# Potentiostat.net
KiCad netlist of a schematic drawn in Altium Designer
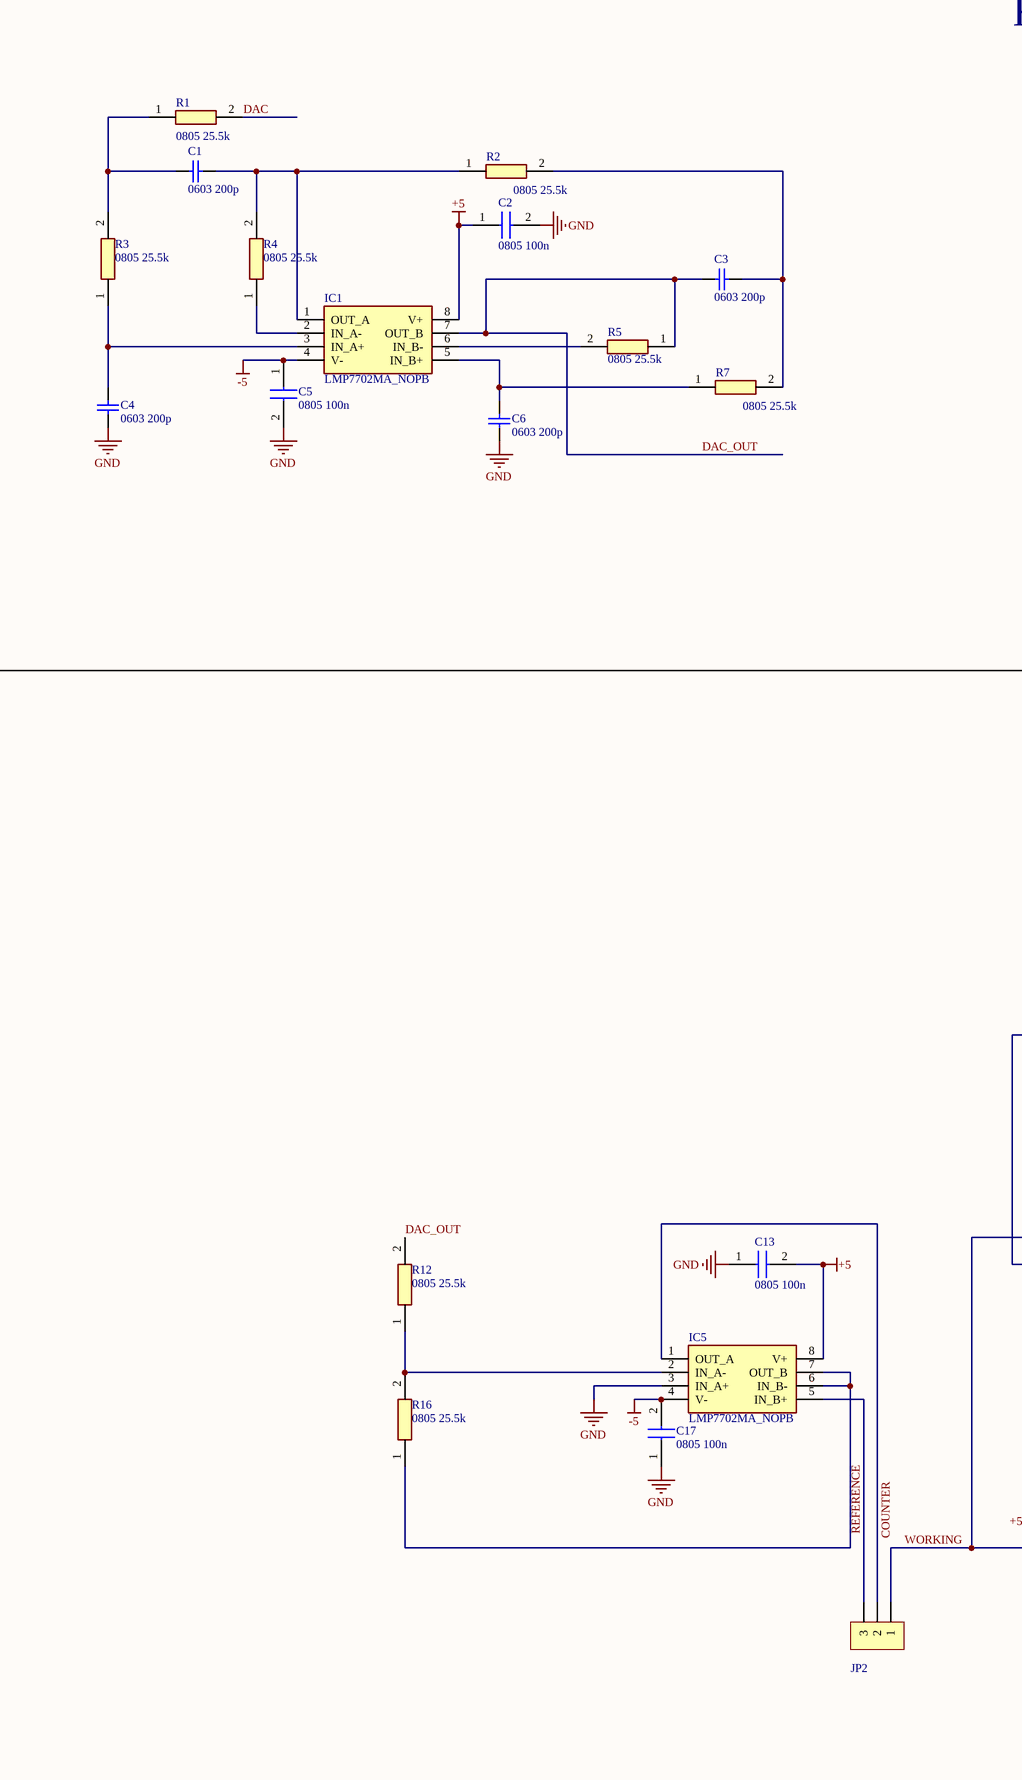
[diagram p0: Potentiostat.SchDoc, left]
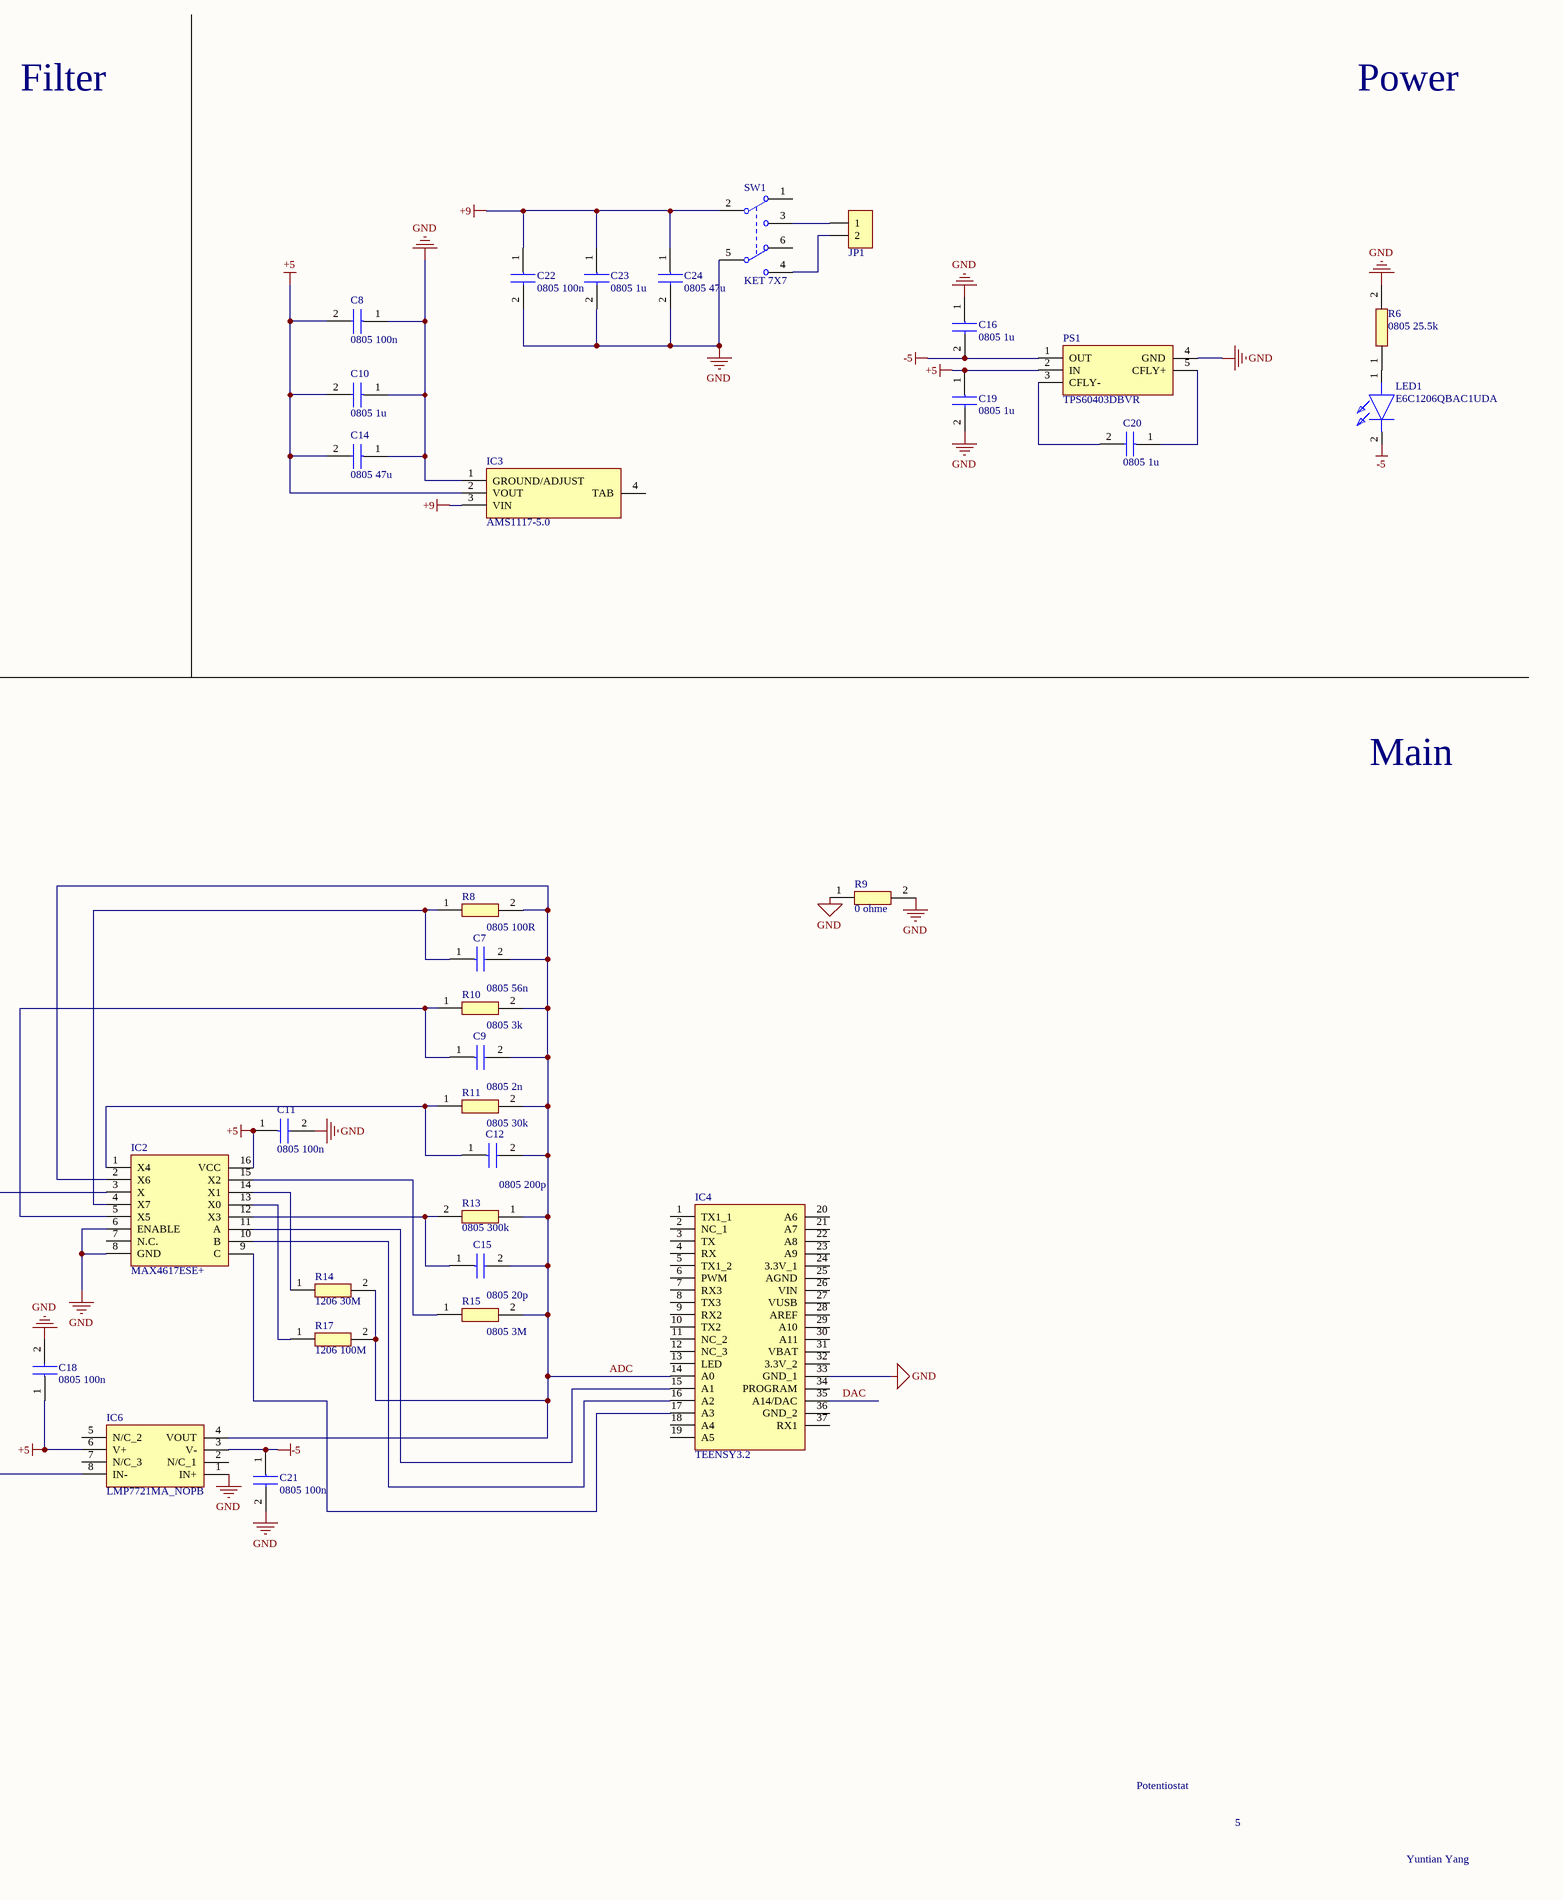
[diagram p1: Potentiostat.SchDoc, right]

(export (version "E")
  (design (tool "Eeschema 10.0.6"))
  (components
    (comp (ref "C1")
      (value "0603 200p")
      (footprint "1608[0603]")
      (description "Capacitor (Semiconductor SIM Model)")
      (fields (field (name "PUBLISHER") "Altium Limited"))
      (libsource (lib "Miscellaneous Devices") (part "Cap Semi"))
    )
    (comp (ref "C2")
      (value "0805 100n")
      (footprint "CAPC2012X130N")
      (description "Capacitor")
      (fields
        (field (name "MANUFACTURER_PART_NUMBER") "C3216X5R1C106K085AC")
        (field (name "MOUSER PART NUMBER") "810-C3216X5R1C106K0C")
      )
      (libsource (lib "time5") (part "C3216X5R1C106K085AC"))
    )
    (comp (ref "C3")
      (value "0603 200p")
      (footprint "1608[0603]")
      (description "Capacitor (Semiconductor SIM Model)")
      (fields (field (name "PUBLISHER") "Altium Limited"))
      (libsource (lib "Miscellaneous Devices") (part "Cap Semi"))
    )
    (comp (ref "C4")
      (value "0603 200p")
      (footprint "1608[0603]")
      (description "Capacitor (Semiconductor SIM Model)")
      (fields (field (name "PUBLISHER") "Altium Limited"))
      (libsource (lib "Miscellaneous Devices") (part "Cap Semi"))
    )
    (comp (ref "C5")
      (value "0805 100n")
      (footprint "CAPC2012X130N")
      (description "Capacitor")
      (fields
        (field (name "MANUFACTURER_PART_NUMBER") "C3216X5R1C106K085AC")
        (field (name "MOUSER PART NUMBER") "810-C3216X5R1C106K0C")
      )
      (libsource (lib "time5") (part "C3216X5R1C106K085AC"))
    )
    (comp (ref "C6")
      (value "0603 200p")
      (footprint "1608[0603]")
      (description "Capacitor (Semiconductor SIM Model)")
      (fields (field (name "PUBLISHER") "Altium Limited"))
      (libsource (lib "Miscellaneous Devices") (part "Cap Semi"))
    )
    (comp (ref "C7")
      (value "0805 56n")
      (footprint "CAPC2012X130N")
      (description "Capacitor")
      (fields
        (field (name "MANUFACTURER_PART_NUMBER") "C3216X5R1C106K085AC")
        (field (name "MOUSER PART NUMBER") "810-C3216X5R1C106K0C")
      )
      (libsource (lib "time5") (part "C3216X5R1C106K085AC"))
    )
    (comp (ref "C8")
      (value "0805 100n")
      (footprint "CAPC2012X130N")
      (description "Capacitor")
      (fields
        (field (name "MANUFACTURER_PART_NUMBER") "C3216X5R1C106K085AC")
        (field (name "MOUSER PART NUMBER") "810-C3216X5R1C106K0C")
      )
      (libsource (lib "time5") (part "C3216X5R1C106K085AC"))
    )
    (comp (ref "C9")
      (value "0805 2n")
      (footprint "CAPC2012X130N")
      (description "Capacitor")
      (fields
        (field (name "MANUFACTURER_PART_NUMBER") "C3216X5R1C106K085AC")
        (field (name "MOUSER PART NUMBER") "810-C3216X5R1C106K0C")
      )
      (libsource (lib "time5") (part "C3216X5R1C106K085AC"))
    )
    (comp (ref "C10")
      (value "0805 1u")
      (footprint "CAPC2012X130N")
      (description "Capacitor")
      (fields
        (field (name "MANUFACTURER_PART_NUMBER") "C3216X5R1C106K085AC")
        (field (name "MOUSER PART NUMBER") "810-C3216X5R1C106K0C")
      )
      (libsource (lib "time5") (part "C3216X5R1C106K085AC"))
    )
    (comp (ref "C11")
      (value "0805 100n")
      (footprint "CAPC2012X130N")
      (description "Capacitor")
      (fields
        (field (name "MANUFACTURER_PART_NUMBER") "C3216X5R1C106K085AC")
        (field (name "MOUSER PART NUMBER") "810-C3216X5R1C106K0C")
      )
      (libsource (lib "time5") (part "C3216X5R1C106K085AC"))
    )
    (comp (ref "C12")
      (value "0805 200p")
      (footprint "CAPC2012X130N")
      (description "Capacitor")
      (fields
        (field (name "MANUFACTURER_PART_NUMBER") "C3216X5R1C106K085AC")
        (field (name "MOUSER PART NUMBER") "810-C3216X5R1C106K0C")
      )
      (libsource (lib "time5") (part "C3216X5R1C106K085AC"))
    )
    (comp (ref "C13")
      (value "0805 100n")
      (footprint "CAPC2012X130N")
      (description "Capacitor")
      (fields
        (field (name "MANUFACTURER_PART_NUMBER") "C3216X5R1C106K085AC")
        (field (name "MOUSER PART NUMBER") "810-C3216X5R1C106K0C")
      )
      (libsource (lib "time5") (part "C3216X5R1C106K085AC"))
    )
    (comp (ref "C14")
      (value "0805 47u")
      (footprint "CAPC2012X130N")
      (description "Capacitor")
      (fields
        (field (name "MANUFACTURER_PART_NUMBER") "C3216X5R1C106K085AC")
        (field (name "MOUSER PART NUMBER") "810-C3216X5R1C106K0C")
      )
      (libsource (lib "time5") (part "C3216X5R1C106K085AC"))
    )
    (comp (ref "C15")
      (value "0805 20p")
      (footprint "CAPC2012X130N")
      (description "Capacitor")
      (fields
        (field (name "MANUFACTURER_PART_NUMBER") "C3216X5R1C106K085AC")
        (field (name "MOUSER PART NUMBER") "810-C3216X5R1C106K0C")
      )
      (libsource (lib "time5") (part "C3216X5R1C106K085AC"))
    )
    (comp (ref "C16")
      (value "0805 1u")
      (footprint "CAPC2012X130N")
      (description "Capacitor")
      (fields
        (field (name "MANUFACTURER_PART_NUMBER") "C3216X5R1C106K085AC")
        (field (name "MOUSER PART NUMBER") "810-C3216X5R1C106K0C")
      )
      (libsource (lib "time5") (part "C3216X5R1C106K085AC"))
    )
    (comp (ref "C17")
      (value "0805 100n")
      (footprint "CAPC2012X130N")
      (description "Capacitor")
      (fields
        (field (name "MANUFACTURER_PART_NUMBER") "C3216X5R1C106K085AC")
        (field (name "MOUSER PART NUMBER") "810-C3216X5R1C106K0C")
      )
      (libsource (lib "time5") (part "C3216X5R1C106K085AC"))
    )
    (comp (ref "C18")
      (value "0805 100n")
      (footprint "CAPC2012X130N")
      (description "Capacitor")
      (fields
        (field (name "MANUFACTURER_PART_NUMBER") "C3216X5R1C106K085AC")
        (field (name "MOUSER PART NUMBER") "810-C3216X5R1C106K0C")
      )
      (libsource (lib "time5") (part "C3216X5R1C106K085AC"))
    )
    (comp (ref "C19")
      (value "0805 1u")
      (footprint "CAPC2012X130N")
      (description "Capacitor")
      (fields
        (field (name "MANUFACTURER_PART_NUMBER") "C3216X5R1C106K085AC")
        (field (name "MOUSER PART NUMBER") "810-C3216X5R1C106K0C")
      )
      (libsource (lib "time5") (part "C3216X5R1C106K085AC"))
    )
    (comp (ref "C20")
      (value "0805 1u")
      (footprint "CAPC2012X130N")
      (description "Capacitor")
      (fields
        (field (name "MANUFACTURER_PART_NUMBER") "C3216X5R1C106K085AC")
        (field (name "MOUSER PART NUMBER") "810-C3216X5R1C106K0C")
      )
      (libsource (lib "time5") (part "C3216X5R1C106K085AC"))
    )
    (comp (ref "C21")
      (value "0805 100n")
      (footprint "CAPC2012X130N")
      (description "Capacitor")
      (fields
        (field (name "MANUFACTURER_PART_NUMBER") "C3216X5R1C106K085AC")
        (field (name "MOUSER PART NUMBER") "810-C3216X5R1C106K0C")
      )
      (libsource (lib "time5") (part "C3216X5R1C106K085AC"))
    )
    (comp (ref "C22")
      (value "0805 100n")
      (footprint "CAPC2012X130N")
      (description "Capacitor")
      (fields
        (field (name "MANUFACTURER_PART_NUMBER") "C3216X5R1C106K085AC")
        (field (name "MOUSER PART NUMBER") "810-C3216X5R1C106K0C")
      )
      (libsource (lib "time5") (part "C3216X5R1C106K085AC"))
    )
    (comp (ref "C23")
      (value "0805 1u")
      (footprint "CAPC2012X130N")
      (description "Capacitor")
      (fields
        (field (name "MANUFACTURER_PART_NUMBER") "C3216X5R1C106K085AC")
        (field (name "MOUSER PART NUMBER") "810-C3216X5R1C106K0C")
      )
      (libsource (lib "time5") (part "C3216X5R1C106K085AC"))
    )
    (comp (ref "C24")
      (value "0805 47u")
      (footprint "CAPC2012X130N")
      (description "Capacitor")
      (fields
        (field (name "MANUFACTURER_PART_NUMBER") "C3216X5R1C106K085AC")
        (field (name "MOUSER PART NUMBER") "810-C3216X5R1C106K0C")
      )
      (libsource (lib "time5") (part "C3216X5R1C106K085AC"))
    )
    (comp (ref "IC1")
      (value "LMP7702MA_NOPB")
      (footprint "SOIC127P600X175-8N")
      (description "Integrated Circuit")
      (fields
        (field (name "MANUFACTURER_PART_NUMBER") "LMP7702MA/NOPB")
        (field (name "MOUSER PART NUMBER") "926-LMP7702MA/NOPB")
      )
      (libsource (lib "time5") (part "LMP7702MA_NOPB"))
    )
    (comp (ref "IC2")
      (value "MAX4617ESE+")
      (footprint "SOIC127P600X175-16N")
      (description "Integrated Circuit")
      (fields (field (name "MOUSER PART NUMBER") "700-MAX4617ESE"))
      (libsource (lib "time5") (part "MAX4617ESE+"))
    )
    (comp (ref "IC3")
      (value "AMS1117-5.0")
      (footprint "SOT229P700X180-4N")
      (description "Integrated Circuit")
      (libsource (lib "time5") (part "AMS1117-5.0"))
    )
    (comp (ref "IC4")
      (value "TEENSY3.2")
      (footprint "TEENSY32")
      (description "Integrated Circuit")
      (libsource (lib "time5") (part "TEENSY3.2"))
    )
    (comp (ref "IC5")
      (value "LMP7702MA_NOPB")
      (footprint "SOIC127P600X175-8N")
      (description "Integrated Circuit")
      (fields
        (field (name "MANUFACTURER_PART_NUMBER") "LMP7702MA/NOPB")
        (field (name "MOUSER PART NUMBER") "926-LMP7702MA/NOPB")
      )
      (libsource (lib "time5") (part "LMP7702MA_NOPB"))
    )
    (comp (ref "IC6")
      (value "LMP7721MA_NOPB")
      (footprint "SOIC127P600X175-8N")
      (description "Integrated Circuit")
      (fields
        (field (name "MANUFACTURER_PART_NUMBER") "LMP7721MA/NOPB")
        (field (name "MOUSER PART NUMBER") "926-LMP7721MA/NOPB")
      )
      (libsource (lib "time5") (part "LMP7721MA_NOPB"))
    )
    (comp (ref "JP1")
      (value "HDR-1X2")
      (footprint "KF2EDGK5.08-LI-2P")
      (description "2P接插件")
      (libsource (lib "6.1 - 接插件-脚距5.08 (200mil) ") (part "Header 2"))
    )
    (comp (ref "JP2")
      (value "HDR-1X3")
      (footprint "KF128-5.08-3P")
      (description "3P接插件")
      (libsource (lib "6.1 - 接插件-脚距5.08 (200mil) ") (part "Header 3"))
    )
    (comp (ref "LED1")
      (value "E6C1206QBAC1UDA")
      (footprint "SamacSys:E6C1206QBAC1UDA")
      (description "LED")
      (libsource (lib "SamacSys") (part "E6C1206QBAC1UDA"))
    )
    (comp (ref "PS1")
      (value "TPS60403DBVR")
      (footprint "SamacSys:SOT95P280X145-5N")
      (description "Power Supply")
      (fields (field (name "MOUSER PART NUMBER") "595-TPS60403DBVR"))
      (libsource (lib "*") (part "TPS60403DBVR"))
    )
    (comp (ref "R1")
      (value "0805 25.5k")
      (footprint "RESC2012X65N")
      (description "Resistor")
      (fields
        (field (name "MANUFACTURER_PART_NUMBER") "PCF0805R-3K24BT1")
        (field (name "MOUSER PART NUMBER") "756-PCF0805R3K24BT1")
      )
      (libsource (lib "") (part "PCF0805R-3K24BT1_1"))
    )
    (comp (ref "R2")
      (value "0805 25.5k")
      (footprint "RESC2012X65N")
      (description "Resistor")
      (fields
        (field (name "MANUFACTURER_PART_NUMBER") "PCF0805R-3K24BT1")
        (field (name "MOUSER PART NUMBER") "756-PCF0805R3K24BT1")
      )
      (libsource (lib "") (part "PCF0805R-3K24BT1_1"))
    )
    (comp (ref "R3")
      (value "0805 25.5k")
      (footprint "RESC2012X65N")
      (description "Resistor")
      (fields
        (field (name "MANUFACTURER_PART_NUMBER") "PCF0805R-3K24BT1")
        (field (name "MOUSER PART NUMBER") "756-PCF0805R3K24BT1")
      )
      (libsource (lib "") (part "PCF0805R-3K24BT1_2"))
    )
    (comp (ref "R4")
      (value "0805 25.5k")
      (footprint "RESC2012X65N")
      (description "Resistor")
      (fields
        (field (name "MANUFACTURER_PART_NUMBER") "PCF0805R-3K24BT1")
        (field (name "MOUSER PART NUMBER") "756-PCF0805R3K24BT1")
      )
      (libsource (lib "") (part "PCF0805R-3K24BT1_2"))
    )
    (comp (ref "R5")
      (value "0805 25.5k")
      (footprint "RESC2012X65N")
      (description "Resistor")
      (fields
        (field (name "MANUFACTURER_PART_NUMBER") "PCF0805R-3K24BT1")
        (field (name "MOUSER PART NUMBER") "756-PCF0805R3K24BT1")
      )
      (libsource (lib "time5") (part "PCF0805R-3K24BT1"))
    )
    (comp (ref "R6")
      (value "0805 25.5k")
      (footprint "RESC2012X65N")
      (description "Resistor")
      (fields
        (field (name "MANUFACTURER_PART_NUMBER") "PCF0805R-3K24BT1")
        (field (name "MOUSER PART NUMBER") "756-PCF0805R3K24BT1")
      )
      (libsource (lib "") (part "PCF0805R-3K24BT1_2"))
    )
    (comp (ref "R7")
      (value "0805 25.5k")
      (footprint "RESC2012X65N")
      (description "Resistor")
      (fields
        (field (name "MANUFACTURER_PART_NUMBER") "PCF0805R-3K24BT1")
        (field (name "MOUSER PART NUMBER") "756-PCF0805R3K24BT1")
      )
      (libsource (lib "") (part "PCF0805R-3K24BT1_1"))
    )
    (comp (ref "R8")
      (value "0805 100R")
      (footprint "RESC2012X65N")
      (description "Resistor")
      (fields
        (field (name "MANUFACTURER_PART_NUMBER") "PCF0805R-3K24BT1")
        (field (name "MOUSER PART NUMBER") "756-PCF0805R3K24BT1")
      )
      (libsource (lib "") (part "PCF0805R-3K24BT1_1"))
    )
    (comp (ref "R9")
      (value "0 ohme")
      (footprint "RESC6331X75N")
      (description "Resistor")
      (fields
        (field (name "MANUFACTURER_PART_NUMBER") "CR2512-F/-1R00ELF")
        (field (name "MOUSER PART NUMBER") "652-CR2512-F/1R00ELF")
      )
      (libsource (lib "time5") (part "CR2512-F_-1R00ELF"))
    )
    (comp (ref "R10")
      (value "0805 3k")
      (footprint "RESC2012X65N")
      (description "Resistor")
      (fields
        (field (name "MANUFACTURER_PART_NUMBER") "PCF0805R-3K24BT1")
        (field (name "MOUSER PART NUMBER") "756-PCF0805R3K24BT1")
      )
      (libsource (lib "") (part "PCF0805R-3K24BT1_1"))
    )
    (comp (ref "R11")
      (value "0805 30k")
      (footprint "RESC2012X65N")
      (description "Resistor")
      (fields
        (field (name "MANUFACTURER_PART_NUMBER") "PCF0805R-3K24BT1")
        (field (name "MOUSER PART NUMBER") "756-PCF0805R3K24BT1")
      )
      (libsource (lib "") (part "PCF0805R-3K24BT1_1"))
    )
    (comp (ref "R12")
      (value "0805 25.5k")
      (footprint "RESC2012X65N")
      (description "Resistor")
      (fields
        (field (name "MANUFACTURER_PART_NUMBER") "PCF0805R-3K24BT1")
        (field (name "MOUSER PART NUMBER") "756-PCF0805R3K24BT1")
      )
      (libsource (lib "") (part "PCF0805R-3K24BT1_2"))
    )
    (comp (ref "R13")
      (value "0805 300k")
      (footprint "RESC2012X65N")
      (description "Resistor")
      (fields
        (field (name "MANUFACTURER_PART_NUMBER") "PCF0805R-3K24BT1")
        (field (name "MOUSER PART NUMBER") "756-PCF0805R3K24BT1")
      )
      (libsource (lib "time5") (part "PCF0805R-3K24BT1"))
    )
    (comp (ref "R14")
      (value "1206 30M")
      (footprint "SamacSys:RESC3216X75N")
      (description "Resistor")
      (fields
        (field (name "MANUFACTURER_PART_NUMBER") "CR1206-F/-2R00ELF")
        (field (name "MOUSER PART NUMBER") "652-CR1206-F/2R00ELF")
      )
      (libsource (lib "*") (part "CR1206-F_-2R00ELF"))
    )
    (comp (ref "R15")
      (value "0805 3M")
      (footprint "RESC2012X65N")
      (description "Resistor")
      (fields
        (field (name "MANUFACTURER_PART_NUMBER") "PCF0805R-3K24BT1")
        (field (name "MOUSER PART NUMBER") "756-PCF0805R3K24BT1")
      )
      (libsource (lib "") (part "PCF0805R-3K24BT1_1"))
    )
    (comp (ref "R16")
      (value "0805 25.5k")
      (footprint "RESC2012X65N")
      (description "Resistor")
      (fields
        (field (name "MANUFACTURER_PART_NUMBER") "PCF0805R-3K24BT1")
        (field (name "MOUSER PART NUMBER") "756-PCF0805R3K24BT1")
      )
      (libsource (lib "") (part "PCF0805R-3K24BT1_2"))
    )
    (comp (ref "R17")
      (value "1206 100M")
      (footprint "SamacSys:RESC3216X75N")
      (description "Resistor")
      (fields
        (field (name "MANUFACTURER_PART_NUMBER") "CR1206-F/-2R00ELF")
        (field (name "MOUSER PART NUMBER") "652-CR1206-F/2R00ELF")
      )
      (libsource (lib "*") (part "CR1206-F_-2R00ELF"))
    )
    (comp (ref "SW1")
      (value "KET 7X7")
      (footprint "KFT DIP-7X7")
      (description "7*7自锁开关")
      (libsource (lib "0.7 - 常用按键-开关-蜂鸣器-电池") (part "KET 7X7"))
    )
  )
  (nets
    (net (code "1") (name "+5") (class "Default")
      (node (ref "C10") (pin "2") (pinfunction "2_2") (pintype "passive"))
      (node (ref "C11") (pin "1") (pinfunction "1_1") (pintype "passive"))
      (node (ref "C13") (pin "2") (pinfunction "2_2") (pintype "passive"))
      (node (ref "C14") (pin "2") (pinfunction "2_2") (pintype "passive"))
      (node (ref "C18") (pin "1") (pinfunction "1_1") (pintype "passive"))
      (node (ref "C19") (pin "1") (pinfunction "1_1") (pintype "passive"))
      (node (ref "C2") (pin "1") (pinfunction "1_1") (pintype "passive"))
      (node (ref "C8") (pin "2") (pinfunction "2_2") (pintype "passive"))
      (node (ref "IC1") (pin "8") (pinfunction "V+_8") (pintype "passive"))
      (node (ref "IC2") (pin "16") (pinfunction "VCC_16") (pintype "passive"))
      (node (ref "IC3") (pin "2") (pinfunction "VOUT_2") (pintype "passive"))
      (node (ref "IC5") (pin "8") (pinfunction "V+_8") (pintype "passive"))
      (node (ref "IC6") (pin "6") (pinfunction "V+_6") (pintype "passive"))
      (node (ref "PS1") (pin "2") (pinfunction "IN_2") (pintype "passive"))
    )
    (net (code "2") (name "+9") (class "Default")
      (node (ref "C22") (pin "1") (pinfunction "1_1") (pintype "passive"))
      (node (ref "C23") (pin "1") (pinfunction "1_1") (pintype "passive"))
      (node (ref "C24") (pin "1") (pinfunction "1_1") (pintype "passive"))
      (node (ref "IC3") (pin "3") (pinfunction "VIN_3") (pintype "passive"))
      (node (ref "SW1") (pin "2") (pinfunction "COM2_2") (pintype "passive"))
    )
    (net (code "3") (name "-5") (class "Default")
      (node (ref "C16") (pin "2") (pinfunction "2_2") (pintype "passive"))
      (node (ref "C17") (pin "2") (pinfunction "2_2") (pintype "passive"))
      (node (ref "C21") (pin "1") (pinfunction "1_1") (pintype "passive"))
      (node (ref "C5") (pin "1") (pinfunction "1_1") (pintype "passive"))
      (node (ref "IC1") (pin "4") (pinfunction "V-_4") (pintype "passive"))
      (node (ref "IC5") (pin "4") (pinfunction "V-_4") (pintype "passive"))
      (node (ref "IC6") (pin "3") (pinfunction "V-_3") (pintype "passive"))
      (node (ref "LED1") (pin "2") (pinfunction "K_2") (pintype "passive"))
      (node (ref "PS1") (pin "1") (pinfunction "OUT_1") (pintype "passive"))
    )
    (net (code "4") (name "/ADC") (class "Default")
      (node (ref "C12") (pin "2") (pinfunction "2_2") (pintype "passive"))
      (node (ref "C15") (pin "2") (pinfunction "2_2") (pintype "passive"))
      (node (ref "C7") (pin "2") (pinfunction "2_2") (pintype "passive"))
      (node (ref "C9") (pin "2") (pinfunction "2_2") (pintype "passive"))
      (node (ref "IC2") (pin "2") (pinfunction "X6_2") (pintype "passive"))
      (node (ref "IC4") (pin "14") (pinfunction "A0_14") (pintype "passive"))
      (node (ref "IC6") (pin "4") (pinfunction "VOUT_4") (pintype "passive"))
      (node (ref "R10") (pin "2") (pinfunction "2_2") (pintype "passive"))
      (node (ref "R11") (pin "2") (pinfunction "2_2") (pintype "passive"))
      (node (ref "R13") (pin "1") (pinfunction "1_1") (pintype "passive"))
      (node (ref "R14") (pin "2") (pinfunction "2_2") (pintype "passive"))
      (node (ref "R15") (pin "2") (pinfunction "2_2") (pintype "passive"))
      (node (ref "R17") (pin "2") (pinfunction "2_2") (pintype "passive"))
      (node (ref "R8") (pin "2") (pinfunction "2_2") (pintype "passive"))
    )
    (net (code "5") (name "/COUNTER") (class "Default")
      (node (ref "IC5") (pin "1") (pinfunction "OUT_A_1") (pintype "passive"))
      (node (ref "JP2") (pin "2") (pinfunction "2_2") (pintype "passive"))
    )
    (net (code "6") (name "/DAC") (class "Default")
      (node (ref "IC4") (pin "35") (pinfunction "A14/DAC_35") (pintype "passive"))
      (node (ref "R1") (pin "2") (pinfunction "2_2") (pintype "passive"))
    )
    (net (code "7") (name "/DAC_OUT") (class "Default")
      (node (ref "C3") (pin "1") (pinfunction "1_1") (pintype "passive"))
      (node (ref "IC1") (pin "7") (pinfunction "OUT_B_7") (pintype "passive"))
      (node (ref "R12") (pin "2") (pinfunction "2_2") (pintype "passive"))
      (node (ref "R5") (pin "1") (pinfunction "1_1") (pintype "passive"))
    )
    (net (code "8") (name "/REFERENCE") (class "Default")
      (node (ref "IC5") (pin "5") (pinfunction "IN_B+_5") (pintype "passive"))
      (node (ref "JP2") (pin "3") (pinfunction "3_3") (pintype "passive"))
    )
    (net (code "9") (name "/WORKING") (class "Default")
      (node (ref "IC2") (pin "3") (pinfunction "X_3") (pintype "passive"))
      (node (ref "IC6") (pin "8") (pinfunction "IN-_8") (pintype "passive"))
      (node (ref "JP2") (pin "1") (pinfunction "1_1") (pintype "passive"))
    )
    (net (code "10") (name "GND") (class "Default")
      (node (ref "C10") (pin "1") (pinfunction "1_1") (pintype "passive"))
      (node (ref "C11") (pin "2") (pinfunction "2_2") (pintype "passive"))
      (node (ref "C13") (pin "1") (pinfunction "1_1") (pintype "passive"))
      (node (ref "C14") (pin "1") (pinfunction "1_1") (pintype "passive"))
      (node (ref "C16") (pin "1") (pinfunction "1_1") (pintype "passive"))
      (node (ref "C17") (pin "1") (pinfunction "1_1") (pintype "passive"))
      (node (ref "C18") (pin "2") (pinfunction "2_2") (pintype "passive"))
      (node (ref "C19") (pin "2") (pinfunction "2_2") (pintype "passive"))
      (node (ref "C2") (pin "2") (pinfunction "2_2") (pintype "passive"))
      (node (ref "C21") (pin "2") (pinfunction "2_2") (pintype "passive"))
      (node (ref "C22") (pin "2") (pinfunction "2_2") (pintype "passive"))
      (node (ref "C23") (pin "2") (pinfunction "2_2") (pintype "passive"))
      (node (ref "C24") (pin "2") (pinfunction "2_2") (pintype "passive"))
      (node (ref "C4") (pin "1") (pinfunction "1_1") (pintype "passive"))
      (node (ref "C5") (pin "2") (pinfunction "2_2") (pintype "passive"))
      (node (ref "C6") (pin "1") (pinfunction "1_1") (pintype "passive"))
      (node (ref "C8") (pin "1") (pinfunction "1_1") (pintype "passive"))
      (node (ref "IC2") (pin "6") (pinfunction "ENABLE_6") (pintype "passive"))
      (node (ref "IC2") (pin "8") (pinfunction "GND_8") (pintype "passive"))
      (node (ref "IC3") (pin "1") (pinfunction "GROUND/ADJUST_1") (pintype "passive"))
      (node (ref "IC4") (pin "33") (pinfunction "GND_1_33") (pintype "passive"))
      (node (ref "IC5") (pin "3") (pinfunction "IN_A+_3") (pintype "passive"))
      (node (ref "IC6") (pin "1") (pinfunction "IN+_1") (pintype "passive"))
      (node (ref "PS1") (pin "4") (pinfunction "GND_4") (pintype "passive"))
      (node (ref "R6") (pin "2") (pinfunction "2_2") (pintype "passive"))
      (node (ref "R9") (pin "1") (pinfunction "1_1") (pintype "passive"))
      (node (ref "R9") (pin "2") (pinfunction "2_2") (pintype "passive"))
      (node (ref "SW1") (pin "5") (pinfunction "COM2_5") (pintype "passive"))
    )
    (net (code "11") (name "Net-(C1-Pad1)") (class "Default")
      (node (ref "C1") (pin "1") (pinfunction "1_1") (pintype "passive"))
      (node (ref "R1") (pin "1") (pinfunction "1_1") (pintype "passive"))
      (node (ref "R3") (pin "2") (pinfunction "2_2") (pintype "passive"))
    )
    (net (code "12") (name "Net-(C3-Pad2)") (class "Default")
      (node (ref "C3") (pin "2") (pinfunction "2_2") (pintype "passive"))
      (node (ref "R2") (pin "2") (pinfunction "2_2") (pintype "passive"))
      (node (ref "R7") (pin "2") (pinfunction "2_2") (pintype "passive"))
    )
    (net (code "13") (name "Net-(IC1-IN_A+)") (class "Default")
      (node (ref "C4") (pin "2") (pinfunction "2_2") (pintype "passive"))
      (node (ref "IC1") (pin "3") (pinfunction "IN_A+_3") (pintype "passive"))
      (node (ref "R3") (pin "1") (pinfunction "1_1") (pintype "passive"))
    )
    (net (code "14") (name "Net-(IC1-IN_A-)") (class "Default")
      (node (ref "IC1") (pin "2") (pinfunction "IN_A-_2") (pintype "passive"))
      (node (ref "R4") (pin "1") (pinfunction "1_1") (pintype "passive"))
    )
    (net (code "15") (name "Net-(IC1-IN_B+)") (class "Default")
      (node (ref "C6") (pin "2") (pinfunction "2_2") (pintype "passive"))
      (node (ref "IC1") (pin "5") (pinfunction "IN_B+_5") (pintype "passive"))
      (node (ref "R7") (pin "1") (pinfunction "1_1") (pintype "passive"))
    )
    (net (code "16") (name "Net-(IC1-IN_B-)") (class "Default")
      (node (ref "IC1") (pin "6") (pinfunction "IN_B-_6") (pintype "passive"))
      (node (ref "R5") (pin "2") (pinfunction "2_2") (pintype "passive"))
    )
    (net (code "17") (name "Net-(IC1-OUT_A)") (class "Default")
      (node (ref "C1") (pin "2") (pinfunction "2_2") (pintype "passive"))
      (node (ref "IC1") (pin "1") (pinfunction "OUT_A_1") (pintype "passive"))
      (node (ref "R2") (pin "1") (pinfunction "1_1") (pintype "passive"))
      (node (ref "R4") (pin "2") (pinfunction "2_2") (pintype "passive"))
    )
    (net (code "18") (name "Net-(IC2-A)") (class "Default")
      (node (ref "IC2") (pin "11") (pinfunction "A_11") (pintype "passive"))
      (node (ref "IC4") (pin "15") (pinfunction "A1_15") (pintype "passive"))
    )
    (net (code "19") (name "Net-(IC2-B)") (class "Default")
      (node (ref "IC2") (pin "10") (pinfunction "B_10") (pintype "passive"))
      (node (ref "IC4") (pin "16") (pinfunction "A2_16") (pintype "passive"))
    )
    (net (code "20") (name "Net-(IC2-C)") (class "Default")
      (node (ref "IC2") (pin "9") (pinfunction "C_9") (pintype "passive"))
      (node (ref "IC4") (pin "17") (pinfunction "A3_17") (pintype "passive"))
    )
    (net (code "21") (name "Net-(IC2-X0)") (class "Default")
      (node (ref "IC2") (pin "13") (pinfunction "X0_13") (pintype "passive"))
      (node (ref "R17") (pin "1") (pinfunction "1_1") (pintype "passive"))
    )
    (net (code "22") (name "Net-(IC2-X1)") (class "Default")
      (node (ref "IC2") (pin "14") (pinfunction "X1_14") (pintype "passive"))
      (node (ref "R14") (pin "1") (pinfunction "1_1") (pintype "passive"))
    )
    (net (code "23") (name "Net-(IC2-X2)") (class "Default")
      (node (ref "IC2") (pin "15") (pinfunction "X2_15") (pintype "passive"))
      (node (ref "R15") (pin "1") (pinfunction "1_1") (pintype "passive"))
    )
    (net (code "24") (name "Net-(IC2-X3)") (class "Default")
      (node (ref "C15") (pin "1") (pinfunction "1_1") (pintype "passive"))
      (node (ref "IC2") (pin "12") (pinfunction "X3_12") (pintype "passive"))
      (node (ref "R13") (pin "2") (pinfunction "2_2") (pintype "passive"))
    )
    (net (code "25") (name "Net-(IC2-X4)") (class "Default")
      (node (ref "C12") (pin "1") (pinfunction "1_1") (pintype "passive"))
      (node (ref "IC2") (pin "1") (pinfunction "X4_1") (pintype "passive"))
      (node (ref "R11") (pin "1") (pinfunction "1_1") (pintype "passive"))
    )
    (net (code "26") (name "Net-(IC2-X5)") (class "Default")
      (node (ref "C9") (pin "1") (pinfunction "1_1") (pintype "passive"))
      (node (ref "IC2") (pin "5") (pinfunction "X5_5") (pintype "passive"))
      (node (ref "R10") (pin "1") (pinfunction "1_1") (pintype "passive"))
    )
    (net (code "27") (name "Net-(IC2-X7)") (class "Default")
      (node (ref "C7") (pin "1") (pinfunction "1_1") (pintype "passive"))
      (node (ref "IC2") (pin "4") (pinfunction "X7_4") (pintype "passive"))
      (node (ref "R8") (pin "1") (pinfunction "1_1") (pintype "passive"))
    )
    (net (code "28") (name "Net-(IC5-IN_A-)") (class "Default")
      (node (ref "IC5") (pin "2") (pinfunction "IN_A-_2") (pintype "passive"))
      (node (ref "R12") (pin "1") (pinfunction "1_1") (pintype "passive"))
      (node (ref "R16") (pin "2") (pinfunction "2_2") (pintype "passive"))
    )
    (net (code "29") (name "Net-(IC5-IN_B-)") (class "Default")
      (node (ref "IC5") (pin "6") (pinfunction "IN_B-_6") (pintype "passive"))
      (node (ref "IC5") (pin "7") (pinfunction "OUT_B_7") (pintype "passive"))
      (node (ref "R16") (pin "1") (pinfunction "1_1") (pintype "passive"))
    )
    (net (code "30") (name "Net-(LED1-A)") (class "Default")
      (node (ref "LED1") (pin "1") (pinfunction "A_1") (pintype "passive"))
      (node (ref "R6") (pin "1") (pinfunction "1_1") (pintype "passive"))
    )
    (net (code "31") (name "Net-(PS1-CFLY+)") (class "Default")
      (node (ref "C20") (pin "1") (pinfunction "1_1") (pintype "passive"))
      (node (ref "PS1") (pin "5") (pinfunction "CFLY+_5") (pintype "passive"))
    )
    (net (code "32") (name "Net-(PS1-CFLY-)") (class "Default")
      (node (ref "C20") (pin "2") (pinfunction "2_2") (pintype "passive"))
      (node (ref "PS1") (pin "3") (pinfunction "CFLY-_3") (pintype "passive"))
    )
    (net (code "33") (name "Net-(SW1-NO1)") (class "Default")
      (node (ref "JP1") (pin "1") (pinfunction "1_1") (pintype "passive"))
      (node (ref "SW1") (pin "3") (pinfunction "NO1_3") (pintype "passive"))
    )
    (net (code "34") (name "Net-(SW1-NO2)") (class "Default")
      (node (ref "JP1") (pin "2") (pinfunction "2_2") (pintype "passive"))
      (node (ref "SW1") (pin "4") (pinfunction "NO2_4") (pintype "passive"))
    )
    (net (code "35") (name "unconnected-(IC2-N.C.-Pad7)") (class "Default")
      (node (ref "IC2") (pin "7") (pinfunction "N.C._7") (pintype "passive"))
    )
    (net (code "36") (name "unconnected-(IC3-TAB-Pad4)") (class "Default")
      (node (ref "IC3") (pin "4") (pinfunction "TAB_4") (pintype "passive"))
    )
    (net (code "37") (name "unconnected-(IC4-3.3V_1-Pad24)") (class "Default")
      (node (ref "IC4") (pin "24") (pinfunction "3.3V_1_24") (pintype "passive"))
    )
    (net (code "38") (name "unconnected-(IC4-3.3V_2-Pad32)") (class "Default")
      (node (ref "IC4") (pin "32") (pinfunction "3.3V_2_32") (pintype "passive"))
    )
    (net (code "39") (name "unconnected-(IC4-A4-Pad18)") (class "Default")
      (node (ref "IC4") (pin "18") (pinfunction "A4_18") (pintype "passive"))
    )
    (net (code "40") (name "unconnected-(IC4-A5-Pad19)") (class "Default")
      (node (ref "IC4") (pin "19") (pinfunction "A5_19") (pintype "passive"))
    )
    (net (code "41") (name "unconnected-(IC4-A6-Pad20)") (class "Default")
      (node (ref "IC4") (pin "20") (pinfunction "A6_20") (pintype "passive"))
    )
    (net (code "42") (name "unconnected-(IC4-A7-Pad21)") (class "Default")
      (node (ref "IC4") (pin "21") (pinfunction "A7_21") (pintype "passive"))
    )
    (net (code "43") (name "unconnected-(IC4-A8-Pad22)") (class "Default")
      (node (ref "IC4") (pin "22") (pinfunction "A8_22") (pintype "passive"))
    )
    (net (code "44") (name "unconnected-(IC4-A9-Pad23)") (class "Default")
      (node (ref "IC4") (pin "23") (pinfunction "A9_23") (pintype "passive"))
    )
    (net (code "45") (name "unconnected-(IC4-A10-Pad29)") (class "Default")
      (node (ref "IC4") (pin "29") (pinfunction "A10_29") (pintype "passive"))
    )
    (net (code "46") (name "unconnected-(IC4-A11-Pad30)") (class "Default")
      (node (ref "IC4") (pin "30") (pinfunction "A11_30") (pintype "passive"))
    )
    (net (code "47") (name "unconnected-(IC4-AGND-Pad25)") (class "Default")
      (node (ref "IC4") (pin "25") (pinfunction "AGND_25") (pintype "passive"))
    )
    (net (code "48") (name "unconnected-(IC4-AREF-Pad28)") (class "Default")
      (node (ref "IC4") (pin "28") (pinfunction "AREF_28") (pintype "passive"))
    )
    (net (code "49") (name "unconnected-(IC4-GND_2-Pad36)") (class "Default")
      (node (ref "IC4") (pin "36") (pinfunction "GND_2_36") (pintype "passive"))
    )
    (net (code "50") (name "unconnected-(IC4-LED-Pad13)") (class "Default")
      (node (ref "IC4") (pin "13") (pinfunction "LED_13") (pintype "passive"))
    )
    (net (code "51") (name "unconnected-(IC4-NC_1-Pad2)") (class "Default")
      (node (ref "IC4") (pin "2") (pinfunction "NC_1_2") (pintype "passive"))
    )
    (net (code "52") (name "unconnected-(IC4-NC_2-Pad11)") (class "Default")
      (node (ref "IC4") (pin "11") (pinfunction "NC_2_11") (pintype "passive"))
    )
    (net (code "53") (name "unconnected-(IC4-NC_3-Pad12)") (class "Default")
      (node (ref "IC4") (pin "12") (pinfunction "NC_3_12") (pintype "passive"))
    )
    (net (code "54") (name "unconnected-(IC4-PROGRAM-Pad34)") (class "Default")
      (node (ref "IC4") (pin "34") (pinfunction "PROGRAM_34") (pintype "passive"))
    )
    (net (code "55") (name "unconnected-(IC4-PWM-Pad6)") (class "Default")
      (node (ref "IC4") (pin "6") (pinfunction "PWM_6") (pintype "passive"))
    )
    (net (code "56") (name "unconnected-(IC4-RX-Pad4)") (class "Default")
      (node (ref "IC4") (pin "4") (pinfunction "RX_4") (pintype "passive"))
    )
    (net (code "57") (name "unconnected-(IC4-RX1-Pad37)") (class "Default")
      (node (ref "IC4") (pin "37") (pinfunction "RX1_37") (pintype "passive"))
    )
    (net (code "58") (name "unconnected-(IC4-RX2-Pad9)") (class "Default")
      (node (ref "IC4") (pin "9") (pinfunction "RX2_9") (pintype "passive"))
    )
    (net (code "59") (name "unconnected-(IC4-RX3-Pad7)") (class "Default")
      (node (ref "IC4") (pin "7") (pinfunction "RX3_7") (pintype "passive"))
    )
    (net (code "60") (name "unconnected-(IC4-TX-Pad3)") (class "Default")
      (node (ref "IC4") (pin "3") (pinfunction "TX_3") (pintype "passive"))
    )
    (net (code "61") (name "unconnected-(IC4-TX1_1-Pad1)") (class "Default")
      (node (ref "IC4") (pin "1") (pinfunction "TX1_1_1") (pintype "passive"))
    )
    (net (code "62") (name "unconnected-(IC4-TX1_2-Pad5)") (class "Default")
      (node (ref "IC4") (pin "5") (pinfunction "TX1_2_5") (pintype "passive"))
    )
    (net (code "63") (name "unconnected-(IC4-TX2-Pad10)") (class "Default")
      (node (ref "IC4") (pin "10") (pinfunction "TX2_10") (pintype "passive"))
    )
    (net (code "64") (name "unconnected-(IC4-TX3-Pad8)") (class "Default")
      (node (ref "IC4") (pin "8") (pinfunction "TX3_8") (pintype "passive"))
    )
    (net (code "65") (name "unconnected-(IC4-VBAT-Pad31)") (class "Default")
      (node (ref "IC4") (pin "31") (pinfunction "VBAT_31") (pintype "passive"))
    )
    (net (code "66") (name "unconnected-(IC4-VIN-Pad26)") (class "Default")
      (node (ref "IC4") (pin "26") (pinfunction "VIN_26") (pintype "passive"))
    )
    (net (code "67") (name "unconnected-(IC4-VUSB-Pad27)") (class "Default")
      (node (ref "IC4") (pin "27") (pinfunction "VUSB_27") (pintype "passive"))
    )
    (net (code "68") (name "unconnected-(IC6-N{slash}C_1-Pad2)") (class "Default")
      (node (ref "IC6") (pin "2") (pinfunction "N/C_1_2") (pintype "passive"))
    )
    (net (code "69") (name "unconnected-(IC6-N{slash}C_2-Pad5)") (class "Default")
      (node (ref "IC6") (pin "5") (pinfunction "N/C_2_5") (pintype "passive"))
    )
    (net (code "70") (name "unconnected-(IC6-N{slash}C_3-Pad7)") (class "Default")
      (node (ref "IC6") (pin "7") (pinfunction "N/C_3_7") (pintype "passive"))
    )
    (net (code "71") (name "unconnected-(SW1-NC1-Pad1)") (class "Default")
      (node (ref "SW1") (pin "1") (pinfunction "NC1_1") (pintype "passive"))
    )
    (net (code "72") (name "unconnected-(SW1-NC2-Pad6)") (class "Default")
      (node (ref "SW1") (pin "6") (pinfunction "NC2_6") (pintype "passive"))
    )
  )
)
